# bot_uc_board_adi.net
KiCad netlist of a schematic drawn in EAGLE
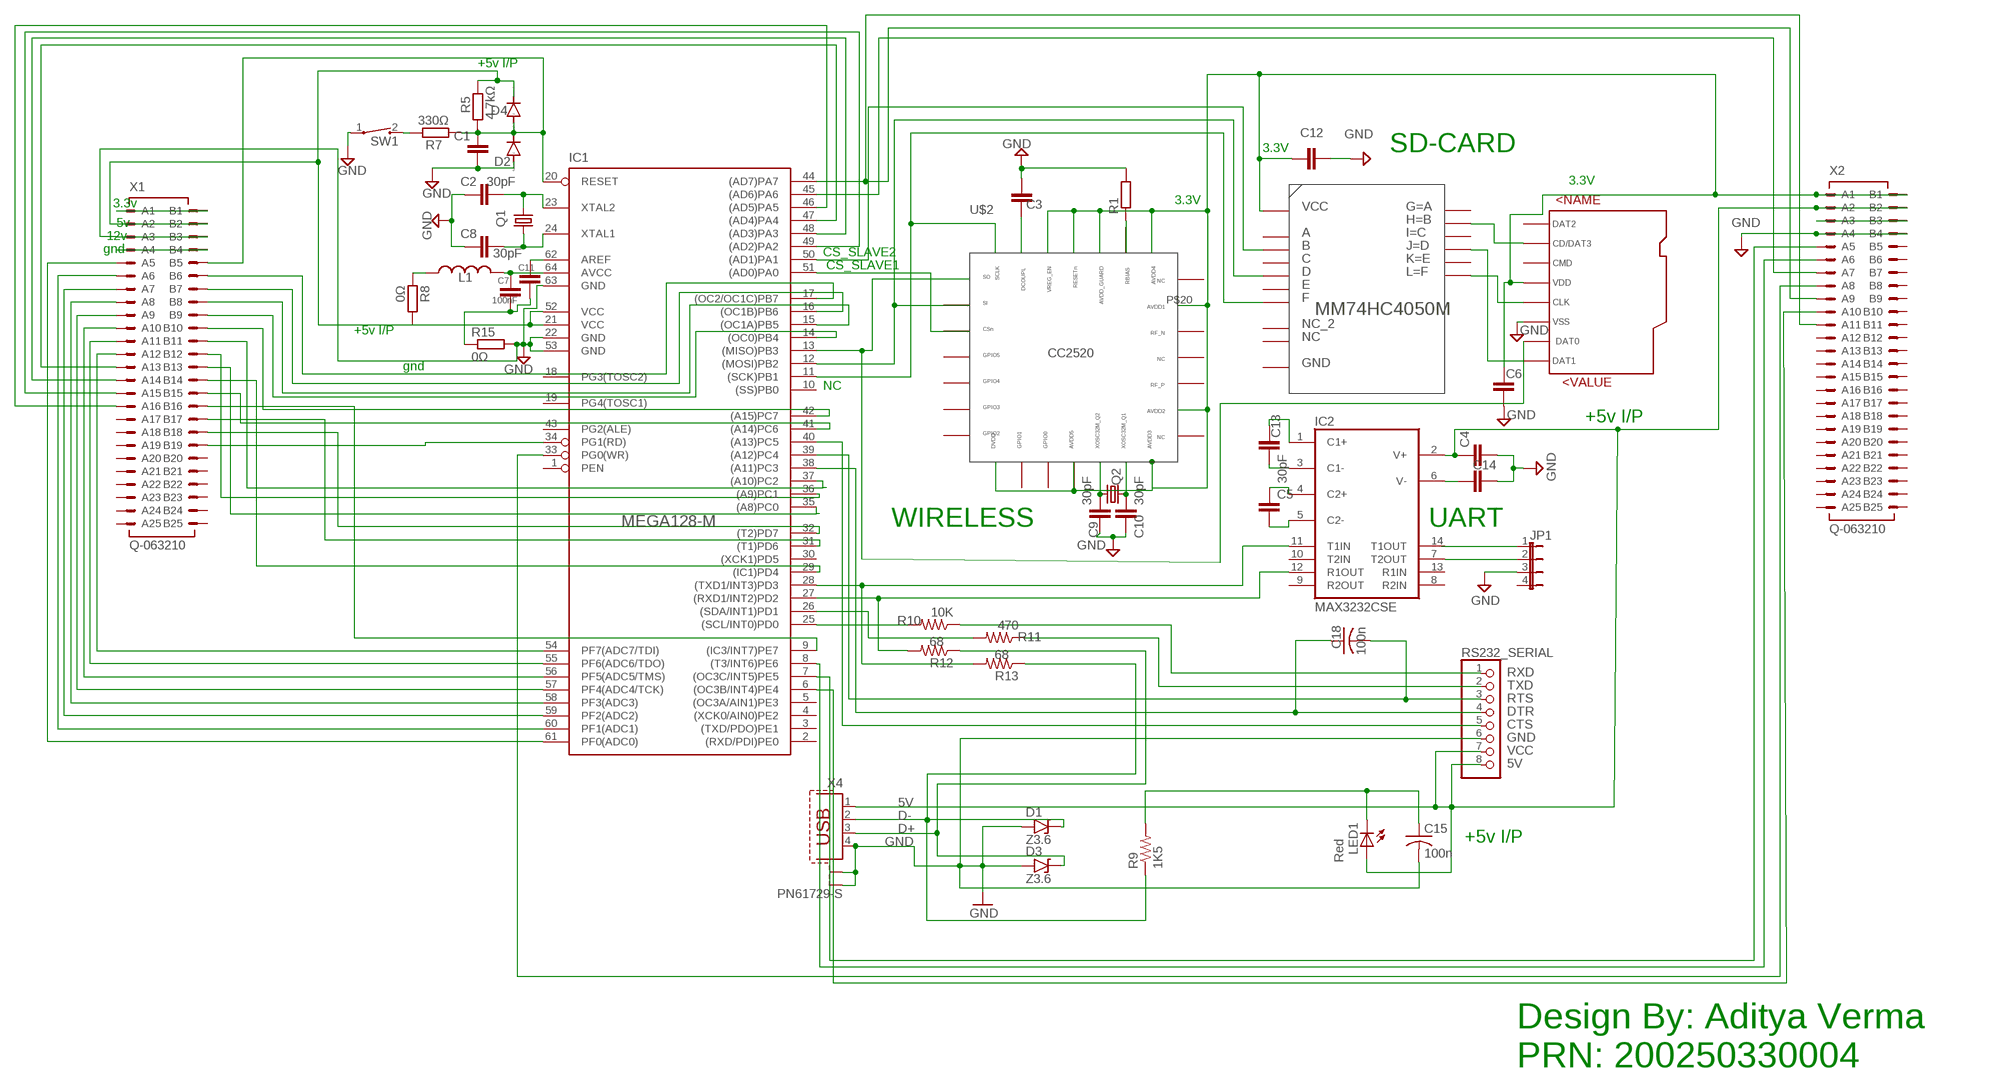
[diagram p0: schematic, sheet 1]

(export (version "E")
  (design (tool "Eeschema 10.0.6"))
  (components
    (comp (ref "C1")
      (value "C-EU025-024X044")
      (footprint "eagle-import:C025-024X044")
      (libsource (lib "eagle-import") (part "C-EU025-024X044"))
    )
    (comp (ref "C2")
      (value "30pF")
      (footprint "eagle-import:C025-024X044")
      (libsource (lib "eagle-import") (part "C-EU025-024X044"))
    )
    (comp (ref "C3")
      (value "C-EU025-024X044")
      (footprint "eagle-import:C025-024X044")
      (libsource (lib "eagle-import") (part "C-EU025-024X044"))
    )
    (comp (ref "C4")
      (value "C-EU025-024X044")
      (footprint "eagle-import:C025-024X044")
      (libsource (lib "eagle-import") (part "C-EU025-024X044"))
    )
    (comp (ref "C5")
      (value "C-EU025-024X044")
      (footprint "eagle-import:C025-024X044")
      (libsource (lib "eagle-import") (part "C-EU025-024X044"))
    )
    (comp (ref "C6")
      (value "30pF")
      (footprint "eagle-import:C025-024X044")
      (libsource (lib "eagle-import") (part "C-EU025-024X044"))
    )
    (comp (ref "C7")
      (value "C-EU025-024X044")
      (footprint "eagle-import:C025-024X044")
      (libsource (lib "eagle-import") (part "C-EU025-024X044"))
    )
    (comp (ref "C8")
      (value "30pF")
      (footprint "eagle-import:C025-024X044")
      (libsource (lib "eagle-import") (part "C-EU025-024X044"))
    )
    (comp (ref "C9")
      (value "30pF")
      (footprint "eagle-import:C025-024X044")
      (libsource (lib "eagle-import") (part "C-EU025-024X044"))
    )
    (comp (ref "C10")
      (value "30pF")
      (footprint "eagle-import:C025-024X044")
      (libsource (lib "eagle-import") (part "C-EU025-024X044"))
    )
    (comp (ref "C11")
      (value "100nF")
      (footprint "eagle-import:C025-024X044")
      (libsource (lib "eagle-import") (part "C-EU025-024X044"))
    )
    (comp (ref "C12")
      (value "C-EU025-024X044")
      (footprint "eagle-import:C025-024X044")
      (libsource (lib "eagle-import") (part "C-EU025-024X044"))
    )
    (comp (ref "C13")
      (value "30pF")
      (footprint "eagle-import:C025-024X044")
      (libsource (lib "eagle-import") (part "C-EU025-024X044"))
    )
    (comp (ref "C14")
      (value "C-EU025-024X044")
      (footprint "eagle-import:C025-024X044")
      (libsource (lib "eagle-import") (part "C-EU025-024X044"))
    )
    (comp (ref "C15")
      (value "100n")
      (footprint "eagle-import:C050-024X044")
      (libsource (lib "eagle-import") (part "C-US050-024X044"))
    )
    (comp (ref "C18")
      (value "100n")
      (footprint "eagle-import:C050-024X044")
      (libsource (lib "eagle-import") (part "C-US050-024X044"))
    )
    (comp (ref "D1")
      (value "Z3.6")
      (footprint "eagle-import:DO35-3")
      (libsource (lib "eagle-import") (part "1N9ZENER"))
    )
    (comp (ref "D2")
      (value "1N4004")
      (footprint "eagle-import:DO41-10")
      (libsource (lib "eagle-import") (part "1N4004"))
    )
    (comp (ref "D3")
      (value "Z3.6")
      (footprint "eagle-import:DO35-3")
      (libsource (lib "eagle-import") (part "1N9ZENER"))
    )
    (comp (ref "D4")
      (value "1N4004")
      (footprint "eagle-import:DO41-10")
      (libsource (lib "eagle-import") (part "1N4004"))
    )
    (comp (ref "IC1")
      (value "MEGA128-M")
      (footprint "eagle-import:MLF64")
      (fields (field (name "MPN") "ATMEGA128-16MU"))
      (libsource (lib "eagle-import") (part "MEGA128-M"))
    )
    (comp (ref "IC2")
      (value "MAX3232CSE")
      (footprint "eagle-import:SO16")
      (libsource (lib "eagle-import") (part "MAX3232SEC"))
    )
    (comp (ref "JP1")
      (value "JP4E")
      (footprint "eagle-import:JP4")
      (libsource (lib "eagle-import") (part "JP4E"))
    )
    (comp (ref "L1")
      (value "L-US0204/5")
      (footprint "eagle-import:0204_5")
      (libsource (lib "eagle-import") (part "L-US0204/5"))
    )
    (comp (ref "LED1")
      (value "Red")
      (footprint "eagle-import:LED3MM")
      (libsource (lib "eagle-import") (part "LED3MM"))
    )
    (comp (ref "Q1")
      (value "CRYSTALHC49U-V")
      (footprint "eagle-import:HC49U-V")
      (libsource (lib "eagle-import") (part "CRYSTALHC49U-V"))
    )
    (comp (ref "Q2")
      (value "CRYSTALHC49U-V")
      (footprint "eagle-import:HC49U-V")
      (libsource (lib "eagle-import") (part "CRYSTALHC49U-V"))
    )
    (comp (ref "R1")
      (value "R-EU_0204/2V")
      (footprint "eagle-import:0204V")
      (libsource (lib "eagle-import") (part "R-EU_0204/2V"))
    )
    (comp (ref "R5")
      (value "4.7kΩ")
      (footprint "eagle-import:0204V")
      (libsource (lib "eagle-import") (part "R-EU_0204/2V"))
    )
    (comp (ref "R7")
      (value "330Ω")
      (footprint "eagle-import:0204V")
      (libsource (lib "eagle-import") (part "R-EU_0204/2V"))
    )
    (comp (ref "R8")
      (value "0Ω")
      (footprint "eagle-import:0204V")
      (libsource (lib "eagle-import") (part "R-EU_0204/2V"))
    )
    (comp (ref "R9")
      (value "1K5")
      (footprint "eagle-import:0207_7")
      (libsource (lib "eagle-import") (part "R-US_0207/7"))
    )
    (comp (ref "R10")
      (value "10K")
      (footprint "eagle-import:0207_7")
      (libsource (lib "eagle-import") (part "R-US_0207/7"))
    )
    (comp (ref "R11")
      (value "470")
      (footprint "eagle-import:0207_7")
      (libsource (lib "eagle-import") (part "R-US_0207/7"))
    )
    (comp (ref "R12")
      (value "68")
      (footprint "eagle-import:0207_7")
      (libsource (lib "eagle-import") (part "R-US_0207/7"))
    )
    (comp (ref "R13")
      (value "68")
      (footprint "eagle-import:0207_7")
      (libsource (lib "eagle-import") (part "R-US_0207/7"))
    )
    (comp (ref "R15")
      (value "0Ω")
      (footprint "eagle-import:0204V")
      (libsource (lib "eagle-import") (part "R-EU_0204/2V"))
    )
    (comp (ref "RS232_SERIAL")
      (value "PINHD-1X8/90")
      (footprint "eagle-import:1X08_90")
      (libsource (lib "eagle-import") (part "PINHD-1X8/90"))
    )
    (comp (ref "SW1")
      (value "CT10-XXXX-A2")
      (footprint "eagle-import:CT10-XXXX-A2")
      (libsource (lib "eagle-import") (part "CT10-XXXX-A2"))
    )
    (comp (ref "U$1")
      (value "74HC4050")
      (footprint "eagle-import:74HC405")
      (libsource (lib "eagle-import") (part "74HC4050"))
    )
    (comp (ref "U$2")
      (value "CC2520")
      (footprint "eagle-import:CC2520_FOOT")
      (libsource (lib "eagle-import") (part "CC2520"))
    )
    (comp (ref "U$3")
      (value "SDCARD")
      (footprint "eagle-import:SDCARD_FOOT")
      (libsource (lib "eagle-import") (part "SDCARD"))
    )
    (comp (ref "X1")
      (value "Q-063210")
      (footprint "eagle-import:063210")
      (libsource (lib "eagle-import") (part "Q-063210"))
    )
    (comp (ref "X2")
      (value "Q-063210")
      (footprint "eagle-import:063210")
      (libsource (lib "eagle-import") (part "Q-063210"))
    )
    (comp (ref "X4")
      (value "PN61729-S")
      (footprint "eagle-import:PN61729-S")
      (libsource (lib "eagle-import") (part "PN61729-S"))
    )
  )
  (nets
    (net (code "1") (name "/D+") (class "Default")
      (node (ref "D3") (pin "C") (pinfunction "C_C") (pintype "passive"))
      (node (ref "R12") (pin "1") (pinfunction "1_1") (pintype "passive"))
      (node (ref "X4") (pin "3") (pinfunction "3_3") (pintype "passive"))
    )
    (net (code "2") (name "/D-") (class "Default")
      (node (ref "D1") (pin "C") (pinfunction "C_C") (pintype "passive"))
      (node (ref "R13") (pin "1") (pinfunction "1_1") (pintype "passive"))
      (node (ref "R9") (pin "1") (pinfunction "1_1") (pintype "passive"))
      (node (ref "X4") (pin "2") (pinfunction "2_2") (pintype "passive"))
    )
    (net (code "3") (name "GND") (class "Default")
      (node (ref "C1") (pin "1") (pinfunction "1_1") (pintype "passive"))
      (node (ref "C10") (pin "1") (pinfunction "1_1") (pintype "passive"))
      (node (ref "C12") (pin "2") (pinfunction "2_2") (pintype "passive"))
      (node (ref "C14") (pin "2") (pinfunction "2_2") (pintype "passive"))
      (node (ref "C15") (pin "2") (pinfunction "2_2") (pintype "passive"))
      (node (ref "C2") (pin "1") (pinfunction "1_1") (pintype "passive"))
      (node (ref "C3") (pin "1") (pinfunction "1_1") (pintype "passive"))
      (node (ref "C4") (pin "2") (pinfunction "2_2") (pintype "passive"))
      (node (ref "C6") (pin "1") (pinfunction "1_1") (pintype "passive"))
      (node (ref "C8") (pin "1") (pinfunction "1_1") (pintype "passive"))
      (node (ref "C9") (pin "1") (pinfunction "1_1") (pintype "passive"))
      (node (ref "D1") (pin "A") (pinfunction "A_A") (pintype "passive"))
      (node (ref "D2") (pin "A") (pinfunction "A_A") (pintype "passive"))
      (node (ref "D3") (pin "A") (pinfunction "A_A") (pintype "passive"))
      (node (ref "IC1") (pin "22") (pinfunction "GND_22") (pintype "power_in"))
      (node (ref "IC1") (pin "53") (pinfunction "GND_53") (pintype "power_in"))
      (node (ref "IC1") (pin "63") (pinfunction "GND_63") (pintype "power_in"))
      (node (ref "JP1") (pin "3") (pinfunction "3_3") (pintype "passive"))
      (node (ref "R1") (pin "2") (pinfunction "2_2") (pintype "passive"))
      (node (ref "R15") (pin "2") (pinfunction "2_2") (pintype "passive"))
      (node (ref "RS232_SERIAL") (pin "6") (pinfunction "6_6") (pintype "passive"))
      (node (ref "SW1") (pin "1") (pinfunction "1_1") (pintype "passive"))
      (node (ref "U$3") (pin "P$6") (pinfunction "VSS_P$6") (pintype "bidirectional"))
      (node (ref "X1") (pin "A3") (pinfunction "A3_A3") (pintype "passive"))
      (node (ref "X1") (pin "B3") (pinfunction "B3_B3") (pintype "passive"))
      (node (ref "X2") (pin "A4") (pinfunction "A4_A4") (pintype "passive"))
      (node (ref "X2") (pin "B4") (pinfunction "B4_B4") (pintype "passive"))
      (node (ref "X4") (pin "4") (pinfunction "4_4") (pintype "passive"))
      (node (ref "X4") (pin "S1") (pinfunction "S1_S1") (pintype "passive"))
      (node (ref "X4") (pin "S2") (pinfunction "S2_S2") (pintype "passive"))
    )
    (net (code "4") (name "Net-(C3-Pad2)") (class "Default")
      (node (ref "C3") (pin "2") (pinfunction "2_2") (pintype "passive"))
      (node (ref "U$2") (pin "P$27") (pinfunction "P$27_P$27") (pintype "bidirectional"))
    )
    (net (code "5") (name "Net-(C9-Pad2)") (class "Default")
      (node (ref "C9") (pin "2") (pinfunction "2_2") (pintype "passive"))
      (node (ref "Q2") (pin "2") (pinfunction "2_2") (pintype "passive"))
      (node (ref "U$2") (pin "P$12") (pinfunction "P$12_P$12") (pintype "bidirectional"))
    )
    (net (code "6") (name "Net-(C10-Pad2)") (class "Default")
      (node (ref "C10") (pin "2") (pinfunction "2_2") (pintype "passive"))
      (node (ref "Q2") (pin "1") (pinfunction "1_1") (pintype "passive"))
      (node (ref "U$2") (pin "P$13") (pinfunction "P$13_P$13") (pintype "bidirectional"))
    )
    (net (code "7") (name "Net-(C11-Pad1)") (class "Default")
      (node (ref "C11") (pin "1") (pinfunction "1_1") (pintype "passive"))
      (node (ref "C7") (pin "2") (pinfunction "2_2") (pintype "passive"))
      (node (ref "R15") (pin "1") (pinfunction "1_1") (pintype "passive"))
    )
    (net (code "8") (name "Net-(D4-PadC)") (class "Default")
      (node (ref "D4") (pin "C") (pinfunction "C_C") (pintype "passive"))
      (node (ref "IC1") (pin "21") (pinfunction "VCC_21") (pintype "power_in"))
      (node (ref "IC1") (pin "52") (pinfunction "VCC_52") (pintype "power_in"))
      (node (ref "R5") (pin "2") (pinfunction "2_2") (pintype "passive"))
      (node (ref "R8") (pin "2") (pinfunction "2_2") (pintype "passive"))
    )
    (net (code "9") (name "Net-(IC1-(A8)PC0)") (class "Default")
      (node (ref "IC1") (pin "35") (pinfunction "(A8)PC0_35") (pintype "output"))
      (node (ref "X1") (pin "B13") (pinfunction "B13_B13") (pintype "passive"))
    )
    (net (code "10") (name "Net-(IC1-(A9)PC1)") (class "Default")
      (node (ref "IC1") (pin "36") (pinfunction "(A9)PC1_36") (pintype "output"))
      (node (ref "X1") (pin "B12") (pinfunction "B12_B12") (pintype "passive"))
    )
    (net (code "11") (name "Net-(IC1-(A10)PC2)") (class "Default")
      (node (ref "IC1") (pin "37") (pinfunction "(A10)PC2_37") (pintype "output"))
      (node (ref "X1") (pin "B11") (pinfunction "B11_B11") (pintype "passive"))
    )
    (net (code "12") (name "Net-(IC1-(A11)PC3)") (class "Default")
      (node (ref "C18") (pin "1") (pinfunction "1_1") (pintype "passive"))
      (node (ref "IC1") (pin "38") (pinfunction "(A11)PC3_38") (pintype "output"))
      (node (ref "RS232_SERIAL") (pin "4") (pinfunction "4_4") (pintype "passive"))
    )
    (net (code "13") (name "Net-(IC1-(A12)PC4)") (class "Default")
      (node (ref "C18") (pin "2") (pinfunction "2_2") (pintype "passive"))
      (node (ref "IC1") (pin "39") (pinfunction "(A12)PC4_39") (pintype "output"))
      (node (ref "RS232_SERIAL") (pin "3") (pinfunction "3_3") (pintype "passive"))
    )
    (net (code "14") (name "Net-(IC1-(A13)PC5)") (class "Default")
      (node (ref "IC1") (pin "40") (pinfunction "(A13)PC5_40") (pintype "output"))
      (node (ref "RS232_SERIAL") (pin "5") (pinfunction "5_5") (pintype "passive"))
    )
    (net (code "15") (name "Net-(IC1-(A14)PC6)") (class "Default")
      (node (ref "IC1") (pin "41") (pinfunction "(A14)PC6_41") (pintype "output"))
      (node (ref "X1") (pin "B15") (pinfunction "B15_B15") (pintype "passive"))
    )
    (net (code "16") (name "Net-(IC1-(A15)PC7)") (class "Default")
      (node (ref "IC1") (pin "42") (pinfunction "(A15)PC7_42") (pintype "output"))
      (node (ref "X1") (pin "B10") (pinfunction "B10_B10") (pintype "passive"))
    )
    (net (code "17") (name "Net-(IC1-(AD0)PA0)") (class "Default")
      (node (ref "IC1") (pin "51") (pinfunction "(AD0)PA0_51") (pintype "bidirectional"))
      (node (ref "U$2") (pin "P$3") (pinfunction "P$3_P$3") (pintype "bidirectional"))
    )
    (net (code "18") (name "Net-(IC1-(AD1)PA1)") (class "Default")
      (node (ref "IC1") (pin "50") (pinfunction "(AD1)PA1_50") (pintype "bidirectional"))
      (node (ref "U$1") (pin "P$5") (pinfunction "B_P$5") (pintype "bidirectional"))
    )
    (net (code "19") (name "Net-(IC1-(AD2)PA2)") (class "Default")
      (node (ref "IC1") (pin "49") (pinfunction "(AD2)PA2_49") (pintype "bidirectional"))
      (node (ref "X1") (pin "A15") (pinfunction "A15_A15") (pintype "passive"))
    )
    (net (code "20") (name "Net-(IC1-(AD3)PA3)") (class "Default")
      (node (ref "IC1") (pin "48") (pinfunction "(AD3)PA3_48") (pintype "bidirectional"))
      (node (ref "X1") (pin "A14") (pinfunction "A14_A14") (pintype "passive"))
    )
    (net (code "21") (name "Net-(IC1-(AD4)PA4)") (class "Default")
      (node (ref "IC1") (pin "47") (pinfunction "(AD4)PA4_47") (pintype "bidirectional"))
      (node (ref "X1") (pin "A13") (pinfunction "A13_A13") (pintype "passive"))
    )
    (net (code "22") (name "Net-(IC1-(AD5)PA5)") (class "Default")
      (node (ref "IC1") (pin "46") (pinfunction "(AD5)PA5_46") (pintype "bidirectional"))
      (node (ref "X1") (pin "A16") (pinfunction "A16_A16") (pintype "passive"))
    )
    (net (code "23") (name "Net-(IC1-(AD6)PA6)") (class "Default")
      (node (ref "IC1") (pin "45") (pinfunction "(AD6)PA6_45") (pintype "bidirectional"))
      (node (ref "X2") (pin "A7") (pinfunction "A7_A7") (pintype "passive"))
    )
    (net (code "24") (name "Net-(IC1-(AD7)PA7)") (class "Default")
      (node (ref "IC1") (pin "44") (pinfunction "(AD7)PA7_44") (pintype "bidirectional"))
      (node (ref "X2") (pin "A11") (pinfunction "A11_A11") (pintype "passive"))
      (node (ref "X2") (pin "A9") (pinfunction "A9_A9") (pintype "passive"))
    )
    (net (code "25") (name "Net-(IC1-(IC1)PD4)") (class "Default")
      (node (ref "IC1") (pin "29") (pinfunction "(IC1)PD4_29") (pintype "bidirectional"))
      (node (ref "X1") (pin "B14") (pinfunction "B14_B14") (pintype "passive"))
    )
    (net (code "26") (name "Net-(IC1-(IC3{slash}INT7)PE7)") (class "Default")
      (node (ref "IC1") (pin "9") (pinfunction "(IC3/INT7)PE7_9") (pintype "bidirectional"))
      (node (ref "X1") (pin "B16") (pinfunction "B16_B16") (pintype "passive"))
    )
    (net (code "27") (name "Net-(IC1-(MISO)PB3)") (class "Default")
      (node (ref "IC1") (pin "13") (pinfunction "(MISO)PB3_13") (pintype "bidirectional"))
      (node (ref "U$2") (pin "P$1") (pinfunction "P$1_P$1") (pintype "bidirectional"))
      (node (ref "U$3") (pin "P$7") (pinfunction "DAT0_P$7") (pintype "bidirectional"))
    )
    (net (code "28") (name "Net-(IC1-(MOSI)PB2)") (class "Default")
      (node (ref "IC1") (pin "12") (pinfunction "(MOSI)PB2_12") (pintype "bidirectional"))
      (node (ref "U$1") (pin "P$9") (pinfunction "D_P$9") (pintype "bidirectional"))
      (node (ref "U$2") (pin "P$2") (pinfunction "P$2_P$2") (pintype "bidirectional"))
    )
    (net (code "29") (name "Net-(IC1-(OC0)PB4)") (class "Default")
      (node (ref "IC1") (pin "14") (pinfunction "(OC0)PB4_14") (pintype "bidirectional"))
      (node (ref "X1") (pin "B9") (pinfunction "B9_B9") (pintype "passive"))
    )
    (net (code "30") (name "Net-(IC1-(OC1A)PB5)") (class "Default")
      (node (ref "IC1") (pin "15") (pinfunction "(OC1A)PB5_15") (pintype "bidirectional"))
      (node (ref "X1") (pin "B8") (pinfunction "B8_B8") (pintype "passive"))
    )
    (net (code "31") (name "Net-(IC1-(OC1B)PB6)") (class "Default")
      (node (ref "IC1") (pin "16") (pinfunction "(OC1B)PB6_16") (pintype "bidirectional"))
      (node (ref "X1") (pin "B7") (pinfunction "B7_B7") (pintype "passive"))
    )
    (net (code "32") (name "Net-(IC1-(OC2{slash}OC1C)PB7)") (class "Default")
      (node (ref "IC1") (pin "17") (pinfunction "(OC2/OC1C)PB7_17") (pintype "bidirectional"))
      (node (ref "X1") (pin "B6") (pinfunction "B6_B6") (pintype "passive"))
    )
    (net (code "33") (name "Net-(IC1-(OC3B{slash}INT4)PE4)") (class "Default")
      (node (ref "IC1") (pin "6") (pinfunction "(OC3B/INT4)PE4_6") (pintype "bidirectional"))
      (node (ref "X2") (pin "A10") (pinfunction "A10_A10") (pintype "passive"))
    )
    (net (code "34") (name "Net-(IC1-(OC3C{slash}INT5)PE5)") (class "Default")
      (node (ref "IC1") (pin "7") (pinfunction "(OC3C/INT5)PE5_7") (pintype "bidirectional"))
      (node (ref "X2") (pin "A5") (pinfunction "A5_A5") (pintype "passive"))
    )
    (net (code "35") (name "Net-(IC1-(RXD1{slash}INT2)PD2)") (class "Default")
      (node (ref "IC1") (pin "27") (pinfunction "(RXD1/INT2)PD2_27") (pintype "bidirectional"))
      (node (ref "IC2") (pin "12") (pinfunction "R1OUT_12") (pintype "output"))
      (node (ref "R12") (pin "2") (pinfunction "2_2") (pintype "passive"))
    )
    (net (code "36") (name "Net-(IC1-(SCK)PB1)") (class "Default")
      (node (ref "IC1") (pin "11") (pinfunction "(SCK)PB1_11") (pintype "bidirectional"))
      (node (ref "U$1") (pin "P$14") (pinfunction "F_P$14") (pintype "bidirectional"))
      (node (ref "U$2") (pin "P$28") (pinfunction "P$28_P$28") (pintype "bidirectional"))
    )
    (net (code "37") (name "Net-(IC1-(SCL{slash}INT0)PD0)") (class "Default")
      (node (ref "IC1") (pin "25") (pinfunction "(SCL/INT0)PD0_25") (pintype "bidirectional"))
      (node (ref "R10") (pin "2") (pinfunction "2_2") (pintype "passive"))
    )
    (net (code "38") (name "Net-(IC1-(SDA{slash}INT1)PD1)") (class "Default")
      (node (ref "IC1") (pin "26") (pinfunction "(SDA/INT1)PD1_26") (pintype "bidirectional"))
      (node (ref "R11") (pin "2") (pinfunction "2_2") (pintype "passive"))
    )
    (net (code "39") (name "Net-(IC1-(T1)PD6)") (class "Default")
      (node (ref "IC1") (pin "31") (pinfunction "(T1)PD6_31") (pintype "bidirectional"))
      (node (ref "X1") (pin "B17") (pinfunction "B17_B17") (pintype "passive"))
    )
    (net (code "40") (name "Net-(IC1-(T2)PD7)") (class "Default")
      (node (ref "IC1") (pin "32") (pinfunction "(T2)PD7_32") (pintype "bidirectional"))
      (node (ref "X1") (pin "B18") (pinfunction "B18_B18") (pintype "passive"))
    )
    (net (code "41") (name "Net-(IC1-(T3{slash}INT6)PE6)") (class "Default")
      (node (ref "IC1") (pin "8") (pinfunction "(T3/INT6)PE6_8") (pintype "bidirectional"))
      (node (ref "X2") (pin "A6") (pinfunction "A6_A6") (pintype "passive"))
    )
    (net (code "42") (name "Net-(IC1-(TXD1{slash}INT3)PD3)") (class "Default")
      (node (ref "IC1") (pin "28") (pinfunction "(TXD1/INT3)PD3_28") (pintype "bidirectional"))
      (node (ref "IC2") (pin "11") (pinfunction "T1IN_11") (pintype "input"))
      (node (ref "R13") (pin "2") (pinfunction "2_2") (pintype "passive"))
    )
    (net (code "43") (name "Net-(IC1-AREF)") (class "Default")
      (node (ref "C11") (pin "2") (pinfunction "2_2") (pintype "passive"))
      (node (ref "IC1") (pin "62") (pinfunction "AREF_62") (pintype "passive"))
    )
    (net (code "44") (name "Net-(IC1-AVCC)") (class "Default")
      (node (ref "C7") (pin "1") (pinfunction "1_1") (pintype "passive"))
      (node (ref "IC1") (pin "64") (pinfunction "AVCC_64") (pintype "power_in"))
      (node (ref "L1") (pin "1") (pinfunction "1_1") (pintype "passive"))
    )
    (net (code "45") (name "Net-(IC1-PF0(ADC0))") (class "Default")
      (node (ref "IC1") (pin "61") (pinfunction "PF0(ADC0)_61") (pintype "input"))
      (node (ref "X1") (pin "A5") (pinfunction "A5_A5") (pintype "passive"))
    )
    (net (code "46") (name "Net-(IC1-PF1(ADC1))") (class "Default")
      (node (ref "IC1") (pin "60") (pinfunction "PF1(ADC1)_60") (pintype "input"))
      (node (ref "X1") (pin "A6") (pinfunction "A6_A6") (pintype "passive"))
    )
    (net (code "47") (name "Net-(IC1-PF2(ADC2))") (class "Default")
      (node (ref "IC1") (pin "59") (pinfunction "PF2(ADC2)_59") (pintype "input"))
      (node (ref "X1") (pin "A7") (pinfunction "A7_A7") (pintype "passive"))
    )
    (net (code "48") (name "Net-(IC1-PF3(ADC3))") (class "Default")
      (node (ref "IC1") (pin "58") (pinfunction "PF3(ADC3)_58") (pintype "input"))
      (node (ref "X1") (pin "A8") (pinfunction "A8_A8") (pintype "passive"))
    )
    (net (code "49") (name "Net-(IC1-PF4(ADC4{slash}TCK))") (class "Default")
      (node (ref "IC1") (pin "57") (pinfunction "PF4(ADC4/TCK)_57") (pintype "input"))
      (node (ref "X1") (pin "A9") (pinfunction "A9_A9") (pintype "passive"))
    )
    (net (code "50") (name "Net-(IC1-PF5(ADC5{slash}TMS))") (class "Default")
      (node (ref "IC1") (pin "56") (pinfunction "PF5(ADC5/TMS)_56") (pintype "input"))
      (node (ref "X1") (pin "A10") (pinfunction "A10_A10") (pintype "passive"))
    )
    (net (code "51") (name "Net-(IC1-PF6(ADC6{slash}TDO))") (class "Default")
      (node (ref "IC1") (pin "55") (pinfunction "PF6(ADC6/TDO)_55") (pintype "input"))
      (node (ref "X1") (pin "A11") (pinfunction "A11_A11") (pintype "passive"))
    )
    (net (code "52") (name "Net-(IC1-PF7(ADC7{slash}TDI))") (class "Default")
      (node (ref "IC1") (pin "54") (pinfunction "PF7(ADC7/TDI)_54") (pintype "input"))
      (node (ref "X1") (pin "A12") (pinfunction "A12_A12") (pintype "passive"))
    )
    (net (code "53") (name "Net-(IC1-PG0(WR))") (class "Default")
      (node (ref "IC1") (pin "33") (pinfunction "PG0(WR)_33") (pintype "bidirectional"))
      (node (ref "X2") (pin "A8") (pinfunction "A8_A8") (pintype "passive"))
    )
    (net (code "54") (name "Net-(IC1-PG1(RD))") (class "Default")
      (node (ref "IC1") (pin "34") (pinfunction "PG1(RD)_34") (pintype "bidirectional"))
      (node (ref "X1") (pin "B19") (pinfunction "B19_B19") (pintype "passive"))
    )
    (net (code "55") (name "Net-(IC1-RESET)") (class "Default")
      (node (ref "D2") (pin "C") (pinfunction "C_C") (pintype "passive"))
      (node (ref "D4") (pin "A") (pinfunction "A_A") (pintype "passive"))
      (node (ref "IC1") (pin "20") (pinfunction "RESET_20") (pintype "input"))
      (node (ref "R5") (pin "1") (pinfunction "1_1") (pintype "passive"))
      (node (ref "R7") (pin "1") (pinfunction "1_1") (pintype "passive"))
      (node (ref "X1") (pin "B5") (pinfunction "B5_B5") (pintype "passive"))
    )
    (net (code "56") (name "Net-(IC1-XTAL1)") (class "Default")
      (node (ref "C8") (pin "2") (pinfunction "2_2") (pintype "passive"))
      (node (ref "IC1") (pin "24") (pinfunction "XTAL1_24") (pintype "bidirectional"))
      (node (ref "Q1") (pin "1") (pinfunction "1_1") (pintype "passive"))
    )
    (net (code "57") (name "Net-(IC1-XTAL2)") (class "Default")
      (node (ref "C2") (pin "2") (pinfunction "2_2") (pintype "passive"))
      (node (ref "IC1") (pin "23") (pinfunction "XTAL2_23") (pintype "bidirectional"))
      (node (ref "Q1") (pin "2") (pinfunction "2_2") (pintype "passive"))
    )
    (net (code "58") (name "Net-(IC2A-C1+)") (class "Default")
      (node (ref "C13") (pin "1") (pinfunction "1_1") (pintype "passive"))
      (node (ref "IC2") (pin "1") (pinfunction "C1+_1") (pintype "bidirectional"))
    )
    (net (code "59") (name "Net-(IC2A-C1-)") (class "Default")
      (node (ref "C13") (pin "2") (pinfunction "2_2") (pintype "passive"))
      (node (ref "IC2") (pin "3") (pinfunction "C1-_3") (pintype "bidirectional"))
    )
    (net (code "60") (name "Net-(IC2A-C2+)") (class "Default")
      (node (ref "C5") (pin "1") (pinfunction "1_1") (pintype "passive"))
      (node (ref "IC2") (pin "4") (pinfunction "C2+_4") (pintype "bidirectional"))
    )
    (net (code "61") (name "Net-(IC2A-C2-)") (class "Default")
      (node (ref "C5") (pin "2") (pinfunction "2_2") (pintype "passive"))
      (node (ref "IC2") (pin "5") (pinfunction "C2-_5") (pintype "bidirectional"))
    )
    (net (code "62") (name "Net-(IC2A-T1OUT)") (class "Default")
      (node (ref "IC2") (pin "14") (pinfunction "T1OUT_14") (pintype "output"))
      (node (ref "JP1") (pin "1") (pinfunction "1_1") (pintype "passive"))
    )
    (net (code "63") (name "Net-(IC2A-T2OUT)") (class "Default")
      (node (ref "IC2") (pin "7") (pinfunction "T2OUT_7") (pintype "output"))
      (node (ref "JP1") (pin "2") (pinfunction "2_2") (pintype "passive"))
    )
    (net (code "64") (name "Net-(IC2A-V+)") (class "Default")
      (node (ref "C4") (pin "1") (pinfunction "1_1") (pintype "passive"))
      (node (ref "IC2") (pin "2") (pinfunction "V+_2") (pintype "bidirectional"))
      (node (ref "LED1") (pin "A") (pinfunction "A_A") (pintype "passive"))
      (node (ref "RS232_SERIAL") (pin "7") (pinfunction "7_7") (pintype "passive"))
      (node (ref "RS232_SERIAL") (pin "8") (pinfunction "8_8") (pintype "passive"))
      (node (ref "X2") (pin "A2") (pinfunction "A2_A2") (pintype "passive"))
      (node (ref "X2") (pin "B2") (pinfunction "B2_B2") (pintype "passive"))
      (node (ref "X4") (pin "1") (pinfunction "1_1") (pintype "passive"))
    )
    (net (code "65") (name "Net-(IC2A-V-)") (class "Default")
      (node (ref "C14") (pin "1") (pinfunction "1_1") (pintype "passive"))
      (node (ref "IC2") (pin "6") (pinfunction "V-_6") (pintype "bidirectional"))
    )
    (net (code "66") (name "Net-(L1-Pad2)") (class "Default")
      (node (ref "L1") (pin "2") (pinfunction "2_2") (pintype "passive"))
      (node (ref "R8") (pin "1") (pinfunction "1_1") (pintype "passive"))
    )
    (net (code "67") (name "Net-(LED1-C)") (class "Default")
      (node (ref "C15") (pin "1") (pinfunction "1_1") (pintype "passive"))
      (node (ref "LED1") (pin "K") (pinfunction "C_K") (pintype "passive"))
      (node (ref "R9") (pin "2") (pinfunction "2_2") (pintype "passive"))
    )
    (net (code "68") (name "Net-(R1-Pad1)") (class "Default")
      (node (ref "R1") (pin "1") (pinfunction "1_1") (pintype "passive"))
      (node (ref "U$2") (pin "P$23") (pinfunction "P$23_P$23") (pintype "bidirectional"))
    )
    (net (code "69") (name "Net-(R7-Pad2)") (class "Default")
      (node (ref "R7") (pin "2") (pinfunction "2_2") (pintype "passive"))
      (node (ref "SW1") (pin "2") (pinfunction "2_2") (pintype "passive"))
    )
    (net (code "70") (name "Net-(R10-Pad1)") (class "Default")
      (node (ref "R10") (pin "1") (pinfunction "1_1") (pintype "passive"))
      (node (ref "RS232_SERIAL") (pin "1") (pinfunction "1_1") (pintype "passive"))
    )
    (net (code "71") (name "Net-(R11-Pad1)") (class "Default")
      (node (ref "R11") (pin "1") (pinfunction "1_1") (pintype "passive"))
      (node (ref "RS232_SERIAL") (pin "2") (pinfunction "2_2") (pintype "passive"))
    )
    (net (code "72") (name "Net-(U$1-H)") (class "Default")
      (node (ref "U$1") (pin "P$4") (pinfunction "H_P$4") (pintype "bidirectional"))
      (node (ref "U$3") (pin "P$2") (pinfunction "CD/DAT3_P$2") (pintype "bidirectional"))
    )
    (net (code "73") (name "Net-(U$1-J)") (class "Default")
      (node (ref "U$1") (pin "P$10") (pinfunction "J_P$10") (pintype "bidirectional"))
      (node (ref "U$3") (pin "P$8") (pinfunction "DAT1_P$8") (pintype "bidirectional"))
    )
    (net (code "74") (name "Net-(U$1-L)") (class "Default")
      (node (ref "U$1") (pin "P$15") (pinfunction "L_P$15") (pintype "bidirectional"))
      (node (ref "U$3") (pin "P$5") (pinfunction "CLK_P$5") (pintype "bidirectional"))
    )
    (net (code "75") (name "Net-(U$1-VCC)") (class "Default")
      (node (ref "C12") (pin "1") (pinfunction "1_1") (pintype "passive"))
      (node (ref "C6") (pin "2") (pinfunction "2_2") (pintype "passive"))
      (node (ref "U$1") (pin "P$1") (pinfunction "VCC_P$1") (pintype "bidirectional"))
      (node (ref "U$2") (pin "P$11") (pinfunction "P$11_P$11") (pintype "bidirectional"))
      (node (ref "U$2") (pin "P$14") (pinfunction "P$14_P$14") (pintype "bidirectional"))
      (node (ref "U$2") (pin "P$16") (pinfunction "P$16_P$16") (pintype "bidirectional"))
      (node (ref "U$2") (pin "P$20") (pinfunction "P$20_P$20") (pintype "bidirectional"))
      (node (ref "U$2") (pin "P$22") (pinfunction "P$22_P$22") (pintype "bidirectional"))
      (node (ref "U$2") (pin "P$24") (pinfunction "P$24_P$24") (pintype "bidirectional"))
      (node (ref "U$2") (pin "P$25") (pinfunction "P$25_P$25") (pintype "bidirectional"))
      (node (ref "U$2") (pin "P$26") (pinfunction "P$26_P$26") (pintype "bidirectional"))
      (node (ref "U$2") (pin "P$8") (pinfunction "P$8_P$8") (pintype "bidirectional"))
      (node (ref "U$3") (pin "P$4") (pinfunction "VDD_P$4") (pintype "bidirectional"))
      (node (ref "X2") (pin "A1") (pinfunction "A1_A1") (pintype "passive"))
      (node (ref "X2") (pin "B1") (pinfunction "B1_B1") (pintype "passive"))
    )
    (net (code "76") (name "Net-(X1-PadA1)") (class "Default")
      (node (ref "X1") (pin "A1") (pinfunction "A1_A1") (pintype "passive"))
      (node (ref "X1") (pin "B1") (pinfunction "B1_B1") (pintype "passive"))
    )
    (net (code "77") (name "Net-(X1-PadA2)") (class "Default")
      (node (ref "X1") (pin "A2") (pinfunction "A2_A2") (pintype "passive"))
      (node (ref "X1") (pin "B2") (pinfunction "B2_B2") (pintype "passive"))
    )
    (net (code "78") (name "Net-(X1-PadA4)") (class "Default")
      (node (ref "X1") (pin "A4") (pinfunction "A4_A4") (pintype "passive"))
      (node (ref "X1") (pin "B4") (pinfunction "B4_B4") (pintype "passive"))
    )
    (net (code "79") (name "Net-(X2-PadA3)") (class "Default")
      (node (ref "X2") (pin "A3") (pinfunction "A3_A3") (pintype "passive"))
      (node (ref "X2") (pin "B3") (pinfunction "B3_B3") (pintype "passive"))
    )
    (net (code "80") (name "unconnected-(C1-Pad2)") (class "Default")
      (node (ref "C1") (pin "2") (pinfunction "2_2") (pintype "passive"))
    )
    (net (code "81") (name "unconnected-(IC1-(OC3A{slash}AIN1)PE3-Pad5)") (class "Default")
      (node (ref "IC1") (pin "5") (pinfunction "(OC3A/AIN1)PE3_5") (pintype "bidirectional"))
    )
    (net (code "82") (name "unconnected-(IC1-(RXD{slash}PDI)PE0-Pad2)") (class "Default")
      (node (ref "IC1") (pin "2") (pinfunction "(RXD/PDI)PE0_2") (pintype "bidirectional"))
    )
    (net (code "83") (name "unconnected-(IC1-(SS)PB0-Pad10)") (class "Default")
      (node (ref "IC1") (pin "10") (pinfunction "(SS)PB0_10") (pintype "bidirectional"))
    )
    (net (code "84") (name "unconnected-(IC1-(TXD{slash}PDO)PE1-Pad3)") (class "Default")
      (node (ref "IC1") (pin "3") (pinfunction "(TXD/PDO)PE1_3") (pintype "bidirectional"))
    )
    (net (code "85") (name "unconnected-(IC1-(XCK0{slash}AIN0)PE2-Pad4)") (class "Default")
      (node (ref "IC1") (pin "4") (pinfunction "(XCK0/AIN0)PE2_4") (pintype "bidirectional"))
    )
    (net (code "86") (name "unconnected-(IC1-(XCK1)PD5-Pad30)") (class "Default")
      (node (ref "IC1") (pin "30") (pinfunction "(XCK1)PD5_30") (pintype "bidirectional"))
    )
    (net (code "87") (name "unconnected-(IC1-PEN-Pad1)") (class "Default")
      (node (ref "IC1") (pin "1") (pinfunction "PEN_1") (pintype "input"))
    )
    (net (code "88") (name "unconnected-(IC1-PG2(ALE)-Pad43)") (class "Default")
      (node (ref "IC1") (pin "43") (pinfunction "PG2(ALE)_43") (pintype "bidirectional"))
    )
    (net (code "89") (name "unconnected-(IC1-PG3(TOSC2)-Pad18)") (class "Default")
      (node (ref "IC1") (pin "18") (pinfunction "PG3(TOSC2)_18") (pintype "bidirectional"))
    )
    (net (code "90") (name "unconnected-(IC1-PG4(TOSC1)-Pad19)") (class "Default")
      (node (ref "IC1") (pin "19") (pinfunction "PG4(TOSC1)_19") (pintype "bidirectional"))
    )
    (net (code "91") (name "unconnected-(IC2A-R1IN-Pad13)") (class "Default")
      (node (ref "IC2") (pin "13") (pinfunction "R1IN_13") (pintype "input"))
    )
    (net (code "92") (name "unconnected-(IC2A-R2IN-Pad8)") (class "Default")
      (node (ref "IC2") (pin "8") (pinfunction "R2IN_8") (pintype "input"))
    )
    (net (code "93") (name "unconnected-(IC2A-R2OUT-Pad9)") (class "Default")
      (node (ref "IC2") (pin "9") (pinfunction "R2OUT_9") (pintype "output"))
    )
    (net (code "94") (name "unconnected-(IC2A-T2IN-Pad10)") (class "Default")
      (node (ref "IC2") (pin "10") (pinfunction "T2IN_10") (pintype "input"))
    )
    (net (code "95") (name "unconnected-(JP1-Pad4)") (class "Default")
      (node (ref "JP1") (pin "4") (pinfunction "4_4") (pintype "passive"))
    )
    (net (code "96") (name "unconnected-(U$1-A-PadP$3)") (class "Default")
      (node (ref "U$1") (pin "P$3") (pinfunction "A_P$3") (pintype "bidirectional"))
    )
    (net (code "97") (name "unconnected-(U$1-C-PadP$7)") (class "Default")
      (node (ref "U$1") (pin "P$7") (pinfunction "C_P$7") (pintype "bidirectional"))
    )
    (net (code "98") (name "unconnected-(U$1-E-PadP$11)") (class "Default")
      (node (ref "U$1") (pin "P$11") (pinfunction "E_P$11") (pintype "bidirectional"))
    )
    (net (code "99") (name "unconnected-(U$1-G-PadP$2)") (class "Default")
      (node (ref "U$1") (pin "P$2") (pinfunction "G_P$2") (pintype "bidirectional"))
    )
    (net (code "100") (name "unconnected-(U$1-GND-PadP$8)") (class "Default")
      (node (ref "U$1") (pin "P$8") (pinfunction "GND_P$8") (pintype "bidirectional"))
    )
    (net (code "101") (name "unconnected-(U$1-I-PadP$6)") (class "Default")
      (node (ref "U$1") (pin "P$6") (pinfunction "I_P$6") (pintype "bidirectional"))
    )
    (net (code "102") (name "unconnected-(U$1-K-PadP$12)") (class "Default")
      (node (ref "U$1") (pin "P$12") (pinfunction "K_P$12") (pintype "bidirectional"))
    )
    (net (code "103") (name "unconnected-(U$1-NC-PadP$16)") (class "Default")
      (node (ref "U$1") (pin "P$16") (pinfunction "NC_P$16") (pintype "bidirectional"))
    )
    (net (code "104") (name "unconnected-(U$1-NC_2-PadP$13)") (class "Default")
      (node (ref "U$1") (pin "P$13") (pinfunction "NC_2_P$13") (pintype "bidirectional"))
    )
    (net (code "105") (name "unconnected-(U$2-PadP$4)") (class "Default")
      (node (ref "U$2") (pin "P$4") (pinfunction "P$4_P$4") (pintype "bidirectional"))
    )
    (net (code "106") (name "unconnected-(U$2-PadP$5)") (class "Default")
      (node (ref "U$2") (pin "P$5") (pinfunction "P$5_P$5") (pintype "bidirectional"))
    )
    (net (code "107") (name "unconnected-(U$2-PadP$6)") (class "Default")
      (node (ref "U$2") (pin "P$6") (pinfunction "P$6_P$6") (pintype "bidirectional"))
    )
    (net (code "108") (name "unconnected-(U$2-PadP$7)") (class "Default")
      (node (ref "U$2") (pin "P$7") (pinfunction "P$7_P$7") (pintype "bidirectional"))
    )
    (net (code "109") (name "unconnected-(U$2-PadP$9)") (class "Default")
      (node (ref "U$2") (pin "P$9") (pinfunction "P$9_P$9") (pintype "bidirectional"))
    )
    (net (code "110") (name "unconnected-(U$2-PadP$10)") (class "Default")
      (node (ref "U$2") (pin "P$10") (pinfunction "P$10_P$10") (pintype "bidirectional"))
    )
    (net (code "111") (name "unconnected-(U$2-PadP$15)") (class "Default")
      (node (ref "U$2") (pin "P$15") (pinfunction "P$15_P$15") (pintype "bidirectional"))
    )
    (net (code "112") (name "unconnected-(U$2-PadP$17)") (class "Default")
      (node (ref "U$2") (pin "P$17") (pinfunction "P$17_P$17") (pintype "bidirectional"))
    )
    (net (code "113") (name "unconnected-(U$2-PadP$18)") (class "Default")
      (node (ref "U$2") (pin "P$18") (pinfunction "P$18_P$18") (pintype "bidirectional"))
    )
    (net (code "114") (name "unconnected-(U$2-PadP$19)") (class "Default")
      (node (ref "U$2") (pin "P$19") (pinfunction "P$19_P$19") (pintype "bidirectional"))
    )
    (net (code "115") (name "unconnected-(U$2-PadP$21)") (class "Default")
      (node (ref "U$2") (pin "P$21") (pinfunction "P$21_P$21") (pintype "bidirectional"))
    )
    (net (code "116") (name "unconnected-(U$3-CMD-PadP$3)") (class "Default")
      (node (ref "U$3") (pin "P$3") (pinfunction "CMD_P$3") (pintype "bidirectional"))
    )
    (net (code "117") (name "unconnected-(U$3-DAT2-PadP$1)") (class "Default")
      (node (ref "U$3") (pin "P$1") (pinfunction "DAT2_P$1") (pintype "bidirectional"))
    )
    (net (code "118") (name "unconnected-(X1-PadA17)") (class "Default")
      (node (ref "X1") (pin "A17") (pinfunction "A17_A17") (pintype "passive"))
    )
    (net (code "119") (name "unconnected-(X1-PadA18)") (class "Default")
      (node (ref "X1") (pin "A18") (pinfunction "A18_A18") (pintype "passive"))
    )
    (net (code "120") (name "unconnected-(X1-PadA19)") (class "Default")
      (node (ref "X1") (pin "A19") (pinfunction "A19_A19") (pintype "passive"))
    )
    (net (code "121") (name "unconnected-(X1-PadA20)") (class "Default")
      (node (ref "X1") (pin "A20") (pinfunction "A20_A20") (pintype "passive"))
    )
    (net (code "122") (name "unconnected-(X1-PadA21)") (class "Default")
      (node (ref "X1") (pin "A21") (pinfunction "A21_A21") (pintype "passive"))
    )
    (net (code "123") (name "unconnected-(X1-PadA22)") (class "Default")
      (node (ref "X1") (pin "A22") (pinfunction "A22_A22") (pintype "passive"))
    )
    (net (code "124") (name "unconnected-(X1-PadA23)") (class "Default")
      (node (ref "X1") (pin "A23") (pinfunction "A23_A23") (pintype "passive"))
    )
    (net (code "125") (name "unconnected-(X1-PadA24)") (class "Default")
      (node (ref "X1") (pin "A24") (pinfunction "A24_A24") (pintype "passive"))
    )
    (net (code "126") (name "unconnected-(X1-PadA25)") (class "Default")
      (node (ref "X1") (pin "A25") (pinfunction "A25_A25") (pintype "passive"))
    )
    (net (code "127") (name "unconnected-(X1-PadB20)") (class "Default")
      (node (ref "X1") (pin "B20") (pinfunction "B20_B20") (pintype "passive"))
    )
    (net (code "128") (name "unconnected-(X1-PadB21)") (class "Default")
      (node (ref "X1") (pin "B21") (pinfunction "B21_B21") (pintype "passive"))
    )
    (net (code "129") (name "unconnected-(X1-PadB22)") (class "Default")
      (node (ref "X1") (pin "B22") (pinfunction "B22_B22") (pintype "passive"))
    )
    (net (code "130") (name "unconnected-(X1-PadB23)") (class "Default")
      (node (ref "X1") (pin "B23") (pinfunction "B23_B23") (pintype "passive"))
    )
    (net (code "131") (name "unconnected-(X1-PadB24)") (class "Default")
      (node (ref "X1") (pin "B24") (pinfunction "B24_B24") (pintype "passive"))
    )
    (net (code "132") (name "unconnected-(X1-PadB25)") (class "Default")
      (node (ref "X1") (pin "B25") (pinfunction "B25_B25") (pintype "passive"))
    )
    (net (code "133") (name "unconnected-(X2-PadA12)") (class "Default")
      (node (ref "X2") (pin "A12") (pinfunction "A12_A12") (pintype "passive"))
    )
    (net (code "134") (name "unconnected-(X2-PadA13)") (class "Default")
      (node (ref "X2") (pin "A13") (pinfunction "A13_A13") (pintype "passive"))
    )
    (net (code "135") (name "unconnected-(X2-PadA14)") (class "Default")
      (node (ref "X2") (pin "A14") (pinfunction "A14_A14") (pintype "passive"))
    )
    (net (code "136") (name "unconnected-(X2-PadA15)") (class "Default")
      (node (ref "X2") (pin "A15") (pinfunction "A15_A15") (pintype "passive"))
    )
    (net (code "137") (name "unconnected-(X2-PadA16)") (class "Default")
      (node (ref "X2") (pin "A16") (pinfunction "A16_A16") (pintype "passive"))
    )
    (net (code "138") (name "unconnected-(X2-PadA17)") (class "Default")
      (node (ref "X2") (pin "A17") (pinfunction "A17_A17") (pintype "passive"))
    )
    (net (code "139") (name "unconnected-(X2-PadA18)") (class "Default")
      (node (ref "X2") (pin "A18") (pinfunction "A18_A18") (pintype "passive"))
    )
    (net (code "140") (name "unconnected-(X2-PadA19)") (class "Default")
      (node (ref "X2") (pin "A19") (pinfunction "A19_A19") (pintype "passive"))
    )
    (net (code "141") (name "unconnected-(X2-PadA20)") (class "Default")
      (node (ref "X2") (pin "A20") (pinfunction "A20_A20") (pintype "passive"))
    )
    (net (code "142") (name "unconnected-(X2-PadA21)") (class "Default")
      (node (ref "X2") (pin "A21") (pinfunction "A21_A21") (pintype "passive"))
    )
    (net (code "143") (name "unconnected-(X2-PadA22)") (class "Default")
      (node (ref "X2") (pin "A22") (pinfunction "A22_A22") (pintype "passive"))
    )
    (net (code "144") (name "unconnected-(X2-PadA23)") (class "Default")
      (node (ref "X2") (pin "A23") (pinfunction "A23_A23") (pintype "passive"))
    )
    (net (code "145") (name "unconnected-(X2-PadA24)") (class "Default")
      (node (ref "X2") (pin "A24") (pinfunction "A24_A24") (pintype "passive"))
    )
    (net (code "146") (name "unconnected-(X2-PadA25)") (class "Default")
      (node (ref "X2") (pin "A25") (pinfunction "A25_A25") (pintype "passive"))
    )
    (net (code "147") (name "unconnected-(X2-PadB5)") (class "Default")
      (node (ref "X2") (pin "B5") (pinfunction "B5_B5") (pintype "passive"))
    )
    (net (code "148") (name "unconnected-(X2-PadB6)") (class "Default")
      (node (ref "X2") (pin "B6") (pinfunction "B6_B6") (pintype "passive"))
    )
    (net (code "149") (name "unconnected-(X2-PadB7)") (class "Default")
      (node (ref "X2") (pin "B7") (pinfunction "B7_B7") (pintype "passive"))
    )
    (net (code "150") (name "unconnected-(X2-PadB8)") (class "Default")
      (node (ref "X2") (pin "B8") (pinfunction "B8_B8") (pintype "passive"))
    )
    (net (code "151") (name "unconnected-(X2-PadB9)") (class "Default")
      (node (ref "X2") (pin "B9") (pinfunction "B9_B9") (pintype "passive"))
    )
    (net (code "152") (name "unconnected-(X2-PadB10)") (class "Default")
      (node (ref "X2") (pin "B10") (pinfunction "B10_B10") (pintype "passive"))
    )
    (net (code "153") (name "unconnected-(X2-PadB11)") (class "Default")
      (node (ref "X2") (pin "B11") (pinfunction "B11_B11") (pintype "passive"))
    )
    (net (code "154") (name "unconnected-(X2-PadB12)") (class "Default")
      (node (ref "X2") (pin "B12") (pinfunction "B12_B12") (pintype "passive"))
    )
    (net (code "155") (name "unconnected-(X2-PadB13)") (class "Default")
      (node (ref "X2") (pin "B13") (pinfunction "B13_B13") (pintype "passive"))
    )
    (net (code "156") (name "unconnected-(X2-PadB14)") (class "Default")
      (node (ref "X2") (pin "B14") (pinfunction "B14_B14") (pintype "passive"))
    )
    (net (code "157") (name "unconnected-(X2-PadB15)") (class "Default")
      (node (ref "X2") (pin "B15") (pinfunction "B15_B15") (pintype "passive"))
    )
    (net (code "158") (name "unconnected-(X2-PadB16)") (class "Default")
      (node (ref "X2") (pin "B16") (pinfunction "B16_B16") (pintype "passive"))
    )
    (net (code "159") (name "unconnected-(X2-PadB17)") (class "Default")
      (node (ref "X2") (pin "B17") (pinfunction "B17_B17") (pintype "passive"))
    )
    (net (code "160") (name "unconnected-(X2-PadB18)") (class "Default")
      (node (ref "X2") (pin "B18") (pinfunction "B18_B18") (pintype "passive"))
    )
    (net (code "161") (name "unconnected-(X2-PadB19)") (class "Default")
      (node (ref "X2") (pin "B19") (pinfunction "B19_B19") (pintype "passive"))
    )
    (net (code "162") (name "unconnected-(X2-PadB20)") (class "Default")
      (node (ref "X2") (pin "B20") (pinfunction "B20_B20") (pintype "passive"))
    )
    (net (code "163") (name "unconnected-(X2-PadB21)") (class "Default")
      (node (ref "X2") (pin "B21") (pinfunction "B21_B21") (pintype "passive"))
    )
    (net (code "164") (name "unconnected-(X2-PadB22)") (class "Default")
      (node (ref "X2") (pin "B22") (pinfunction "B22_B22") (pintype "passive"))
    )
    (net (code "165") (name "unconnected-(X2-PadB23)") (class "Default")
      (node (ref "X2") (pin "B23") (pinfunction "B23_B23") (pintype "passive"))
    )
    (net (code "166") (name "unconnected-(X2-PadB24)") (class "Default")
      (node (ref "X2") (pin "B24") (pinfunction "B24_B24") (pintype "passive"))
    )
    (net (code "167") (name "unconnected-(X2-PadB25)") (class "Default")
      (node (ref "X2") (pin "B25") (pinfunction "B25_B25") (pintype "passive"))
    )
  )
)
